# TEMPSENS.net
KiCad netlist of a schematic drawn in Altium Designer
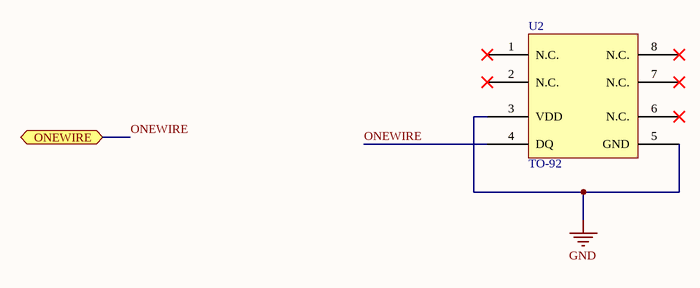
[diagram p0: TEMPSENS.SchDoc]

(export (version "E")
  (design (tool "Eeschema 10.0.6"))
  (components
    (comp (ref "U2")
      (value "TO-92")
      (footprint "DS18S20")
      (description "1-Wire Digital Thermometer")
      (libsource (lib "Telemetry") (part "DS18S20"))
    )
  )
  (nets
    (net (code "1") (name "/ONEWIRE") (class "Default")
      (node (ref "U2") (pin "4") (pinfunction "DQ_4") (pintype "passive"))
    )
    (net (code "2") (name "GND") (class "Default")
      (node (ref "U2") (pin "3") (pinfunction "VDD_3") (pintype "passive"))
      (node (ref "U2") (pin "5") (pinfunction "GND_5") (pintype "passive"))
    )
    (net (code "3") (name "unconnected-(U2-N.C.-Pad1)") (class "Default")
      (node (ref "U2") (pin "1") (pinfunction "N.C._1") (pintype "passive+no_connect"))
    )
    (net (code "4") (name "unconnected-(U2-N.C.-Pad2)") (class "Default")
      (node (ref "U2") (pin "2") (pinfunction "N.C._2") (pintype "passive+no_connect"))
    )
    (net (code "5") (name "unconnected-(U2-N.C.-Pad6)") (class "Default")
      (node (ref "U2") (pin "6") (pinfunction "N.C._6") (pintype "passive+no_connect"))
    )
    (net (code "6") (name "unconnected-(U2-N.C.-Pad7)") (class "Default")
      (node (ref "U2") (pin "7") (pinfunction "N.C._7") (pintype "passive+no_connect"))
    )
    (net (code "7") (name "unconnected-(U2-N.C.-Pad8)") (class "Default")
      (node (ref "U2") (pin "8") (pinfunction "N.C._8") (pintype "passive+no_connect"))
    )
  )
)
